# Stearns.net
KiCad netlist of a schematic drawn in EAGLE
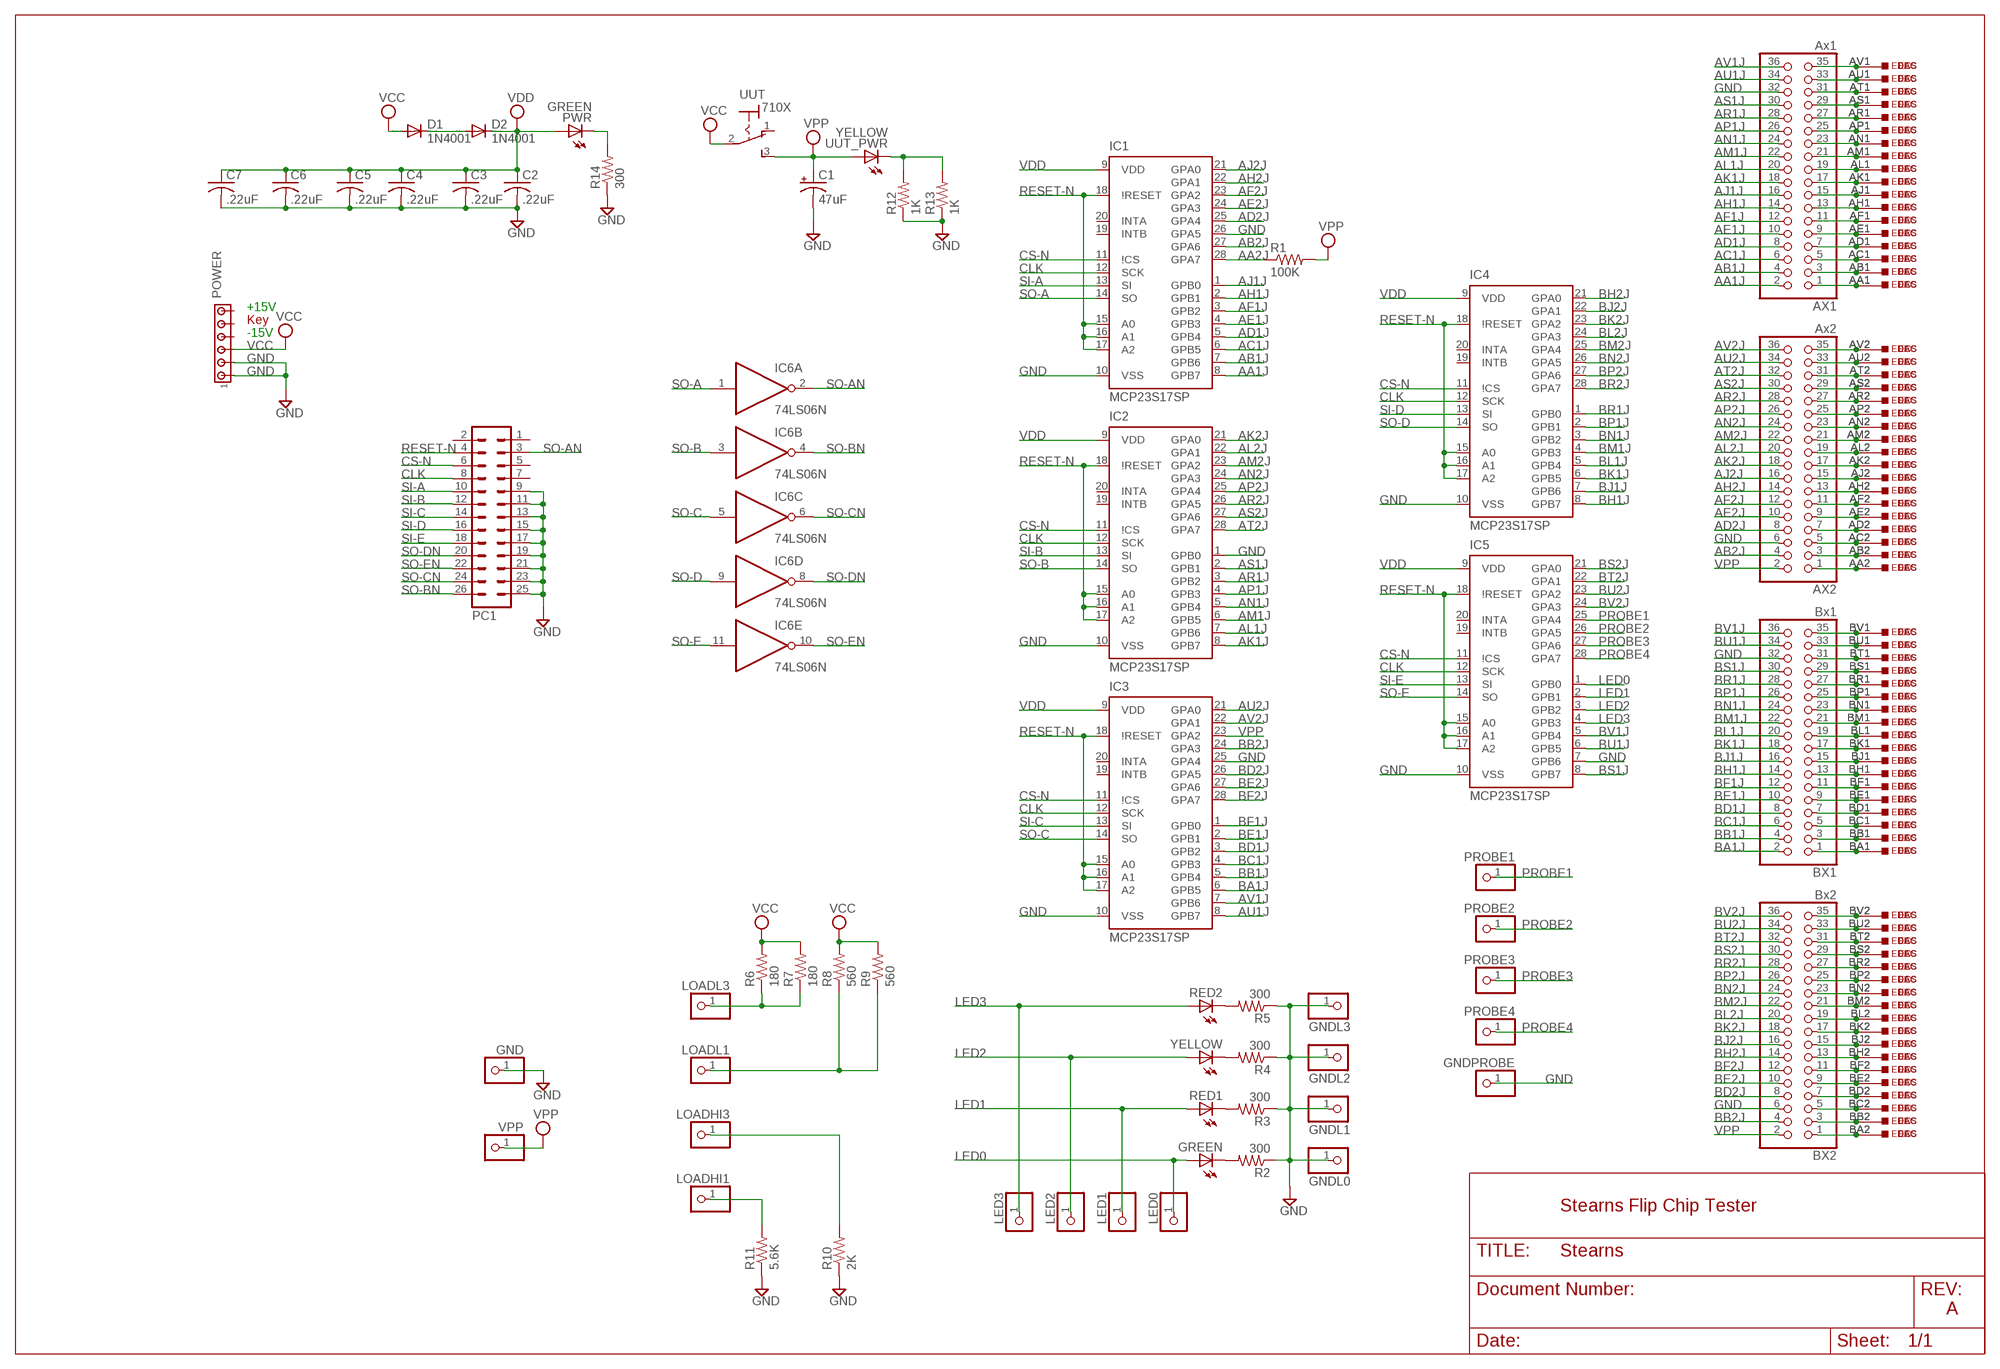
[diagram p0: schematic, sheet 1]

(export (version "E")
  (design (tool "Eeschema 10.0.6"))
  (components
    (comp (ref "AX1")
      (value "Ax1")
      (footprint "eagle-import:2X18")
      (libsource (lib "eagle-import") (part "PINHD-2X18"))
    )
    (comp (ref "AX2")
      (value "Ax2")
      (footprint "eagle-import:2X18")
      (libsource (lib "eagle-import") (part "PINHD-2X18"))
    )
    (comp (ref "BX1")
      (value "Bx1")
      (footprint "eagle-import:2X18")
      (libsource (lib "eagle-import") (part "PINHD-2X18"))
    )
    (comp (ref "BX2")
      (value "Bx2")
      (footprint "eagle-import:2X18")
      (libsource (lib "eagle-import") (part "PINHD-2X18"))
    )
    (comp (ref "C1")
      (value "47uF")
      (footprint "eagle-import:E5-8,5")
      (libsource (lib "eagle-import") (part "CPOL-USE5-8.5"))
    )
    (comp (ref "C2")
      (value ".22uF")
      (footprint "eagle-import:C050-025X075")
      (libsource (lib "eagle-import") (part "C-US050-025X075"))
    )
    (comp (ref "C3")
      (value ".22uF")
      (footprint "eagle-import:C050-025X075")
      (libsource (lib "eagle-import") (part "C-US050-025X075"))
    )
    (comp (ref "C4")
      (value ".22uF")
      (footprint "eagle-import:C050-025X075")
      (libsource (lib "eagle-import") (part "C-US050-025X075"))
    )
    (comp (ref "C5")
      (value ".22uF")
      (footprint "eagle-import:C050-025X075")
      (libsource (lib "eagle-import") (part "C-US050-025X075"))
    )
    (comp (ref "C6")
      (value ".22uF")
      (footprint "eagle-import:C050-025X075")
      (libsource (lib "eagle-import") (part "C-US050-025X075"))
    )
    (comp (ref "C7")
      (value ".22uF")
      (footprint "eagle-import:C050-025X075")
      (libsource (lib "eagle-import") (part "C-US050-025X075"))
    )
    (comp (ref "D1")
      (value "1N4001")
      (footprint "eagle-import:DO41-10")
      (libsource (lib "eagle-import") (part "1N4004"))
    )
    (comp (ref "D2")
      (value "1N4001")
      (footprint "eagle-import:DO41-10")
      (libsource (lib "eagle-import") (part "1N4004"))
    )
    (comp (ref "DEC")
      (value "W971")
      (footprint "eagle-import:H807-2")
      (libsource (lib "eagle-import") (part "W971"))
    )
    (comp (ref "ECS")
      (value "W971ECS")
      (footprint "eagle-import:ECS2418-2")
      (libsource (lib "eagle-import") (part "W971ECS"))
    )
    (comp (ref "EDAC")
      (value "W971EDAC")
      (footprint "eagle-import:EDAC346-36-2")
      (libsource (lib "eagle-import") (part "W971EDAC"))
    )
    (comp (ref "GND")
      (value "PINHD-1X1")
      (footprint "eagle-import:1X01")
      (libsource (lib "eagle-import") (part "PINHD-1X1"))
    )
    (comp (ref "GNDL0")
      (value "PINHD-1X1")
      (footprint "eagle-import:1X01")
      (libsource (lib "eagle-import") (part "PINHD-1X1"))
    )
    (comp (ref "GNDL1")
      (value "PINHD-1X1")
      (footprint "eagle-import:1X01")
      (libsource (lib "eagle-import") (part "PINHD-1X1"))
    )
    (comp (ref "GNDL2")
      (value "PINHD-1X1")
      (footprint "eagle-import:1X01")
      (libsource (lib "eagle-import") (part "PINHD-1X1"))
    )
    (comp (ref "GNDL3")
      (value "PINHD-1X1")
      (footprint "eagle-import:1X01")
      (libsource (lib "eagle-import") (part "PINHD-1X1"))
    )
    (comp (ref "GNDPROBE")
      (value "PINHD-1X1")
      (footprint "eagle-import:1X01")
      (libsource (lib "eagle-import") (part "PINHD-1X1"))
    )
    (comp (ref "GREEN")
      (value "LED5MM")
      (footprint "eagle-import:LED5MM")
      (libsource (lib "eagle-import") (part "LED5MM"))
    )
    (comp (ref "IC1")
      (value "MCP23S17SP")
      (footprint "eagle-import:DIL28-3")
      (libsource (lib "eagle-import") (part "MCP23S17SP"))
    )
    (comp (ref "IC2")
      (value "MCP23S17SP")
      (footprint "eagle-import:DIL28-3")
      (libsource (lib "eagle-import") (part "MCP23S17SP"))
    )
    (comp (ref "IC3")
      (value "MCP23S17SP")
      (footprint "eagle-import:DIL28-3")
      (libsource (lib "eagle-import") (part "MCP23S17SP"))
    )
    (comp (ref "IC4")
      (value "MCP23S17SP")
      (footprint "eagle-import:DIL28-3")
      (libsource (lib "eagle-import") (part "MCP23S17SP"))
    )
    (comp (ref "IC5")
      (value "MCP23S17SP")
      (footprint "eagle-import:DIL28-3")
      (libsource (lib "eagle-import") (part "MCP23S17SP"))
    )
    (comp (ref "IC6")
      (value "74LS06N")
      (footprint "eagle-import:DIL14")
      (libsource (lib "eagle-import") (part "7406NLS"))
    )
    (comp (ref "LED0")
      (value "PINHD-1X1")
      (footprint "eagle-import:1X01")
      (libsource (lib "eagle-import") (part "PINHD-1X1"))
    )
    (comp (ref "LED1")
      (value "PINHD-1X1")
      (footprint "eagle-import:1X01")
      (libsource (lib "eagle-import") (part "PINHD-1X1"))
    )
    (comp (ref "LED2")
      (value "PINHD-1X1")
      (footprint "eagle-import:1X01")
      (libsource (lib "eagle-import") (part "PINHD-1X1"))
    )
    (comp (ref "LED3")
      (value "PINHD-1X1")
      (footprint "eagle-import:1X01")
      (libsource (lib "eagle-import") (part "PINHD-1X1"))
    )
    (comp (ref "LOADHI1")
      (value "PINHD-1X1")
      (footprint "eagle-import:1X01")
      (libsource (lib "eagle-import") (part "PINHD-1X1"))
    )
    (comp (ref "LOADHI3")
      (value "PINHD-1X1")
      (footprint "eagle-import:1X01")
      (libsource (lib "eagle-import") (part "PINHD-1X1"))
    )
    (comp (ref "LOADL1")
      (value "PINHD-1X1")
      (footprint "eagle-import:1X01")
      (libsource (lib "eagle-import") (part "PINHD-1X1"))
    )
    (comp (ref "LOADL3")
      (value "PINHD-1X1")
      (footprint "eagle-import:1X01")
      (libsource (lib "eagle-import") (part "PINHD-1X1"))
    )
    (comp (ref "PC1")
      (value "MA13-2")
      (footprint "eagle-import:MA13-2")
      (libsource (lib "eagle-import") (part "MA13-2"))
    )
    (comp (ref "POWER")
      (value "MTA06-156")
      (footprint "eagle-import:1X6MTA")
      (libsource (lib "eagle-import") (part "MTA06-156"))
    )
    (comp (ref "PROBE1")
      (value "PINHD-1X1")
      (footprint "eagle-import:1X01")
      (libsource (lib "eagle-import") (part "PINHD-1X1"))
    )
    (comp (ref "PROBE2")
      (value "PINHD-1X1")
      (footprint "eagle-import:1X01")
      (libsource (lib "eagle-import") (part "PINHD-1X1"))
    )
    (comp (ref "PROBE3")
      (value "PINHD-1X1")
      (footprint "eagle-import:1X01")
      (libsource (lib "eagle-import") (part "PINHD-1X1"))
    )
    (comp (ref "PROBE4")
      (value "PINHD-1X1")
      (footprint "eagle-import:1X01")
      (libsource (lib "eagle-import") (part "PINHD-1X1"))
    )
    (comp (ref "PWR")
      (value "GREEN")
      (footprint "eagle-import:LED5MM")
      (libsource (lib "eagle-import") (part "LED5MM"))
    )
    (comp (ref "R1")
      (value "100K")
      (footprint "eagle-import:0207_10")
      (libsource (lib "eagle-import") (part "R-US_0207/10"))
    )
    (comp (ref "R2")
      (value "300")
      (footprint "eagle-import:0207_10")
      (libsource (lib "eagle-import") (part "R-US_0207/10"))
    )
    (comp (ref "R3")
      (value "300")
      (footprint "eagle-import:0207_10")
      (libsource (lib "eagle-import") (part "R-US_0207/10"))
    )
    (comp (ref "R4")
      (value "300")
      (footprint "eagle-import:0207_10")
      (libsource (lib "eagle-import") (part "R-US_0207/10"))
    )
    (comp (ref "R5")
      (value "300")
      (footprint "eagle-import:0207_10")
      (libsource (lib "eagle-import") (part "R-US_0207/10"))
    )
    (comp (ref "R6")
      (value "180")
      (footprint "eagle-import:0207_10")
      (libsource (lib "eagle-import") (part "R-US_0207/10"))
    )
    (comp (ref "R7")
      (value "180")
      (footprint "eagle-import:0207_10")
      (libsource (lib "eagle-import") (part "R-US_0207/10"))
    )
    (comp (ref "R8")
      (value "560")
      (footprint "eagle-import:0207_10")
      (libsource (lib "eagle-import") (part "R-US_0207/10"))
    )
    (comp (ref "R9")
      (value "560")
      (footprint "eagle-import:0207_10")
      (libsource (lib "eagle-import") (part "R-US_0207/10"))
    )
    (comp (ref "R10")
      (value "2K")
      (footprint "eagle-import:0207_10")
      (libsource (lib "eagle-import") (part "R-US_0207/10"))
    )
    (comp (ref "R11")
      (value "5.6K")
      (footprint "eagle-import:0207_10")
      (libsource (lib "eagle-import") (part "R-US_0207/10"))
    )
    (comp (ref "R12")
      (value "1K")
      (footprint "eagle-import:0207_10")
      (libsource (lib "eagle-import") (part "R-US_0207/10"))
    )
    (comp (ref "R13")
      (value "1K")
      (footprint "eagle-import:0207_10")
      (libsource (lib "eagle-import") (part "R-US_0207/10"))
    )
    (comp (ref "R14")
      (value "300")
      (footprint "eagle-import:0207_10")
      (libsource (lib "eagle-import") (part "R-US_0207/10"))
    )
    (comp (ref "RED1")
      (value "LED5MM")
      (footprint "eagle-import:LED5MM")
      (libsource (lib "eagle-import") (part "LED5MM"))
    )
    (comp (ref "RED2")
      (value "LED5MM")
      (footprint "eagle-import:LED5MM")
      (libsource (lib "eagle-import") (part "LED5MM"))
    )
    (comp (ref "UUT")
      (value "710X")
      (footprint "eagle-import:7109MD9V3")
      (libsource (lib "eagle-import") (part "710X"))
    )
    (comp (ref "UUT_PWR")
      (value "YELLOW")
      (footprint "eagle-import:LED5MM")
      (libsource (lib "eagle-import") (part "LED5MM"))
    )
    (comp (ref "VPP")
      (value "PINHD-1X1")
      (footprint "eagle-import:1X01")
      (libsource (lib "eagle-import") (part "PINHD-1X1"))
    )
    (comp (ref "YELLOW")
      (value "LED5MM")
      (footprint "eagle-import:LED5MM")
      (libsource (lib "eagle-import") (part "LED5MM"))
    )
  )
  (nets
    (net (code "1") (name "/AA1J") (class "Default")
      (node (ref "AX1") (pin "2") (pinfunction "2_2") (pintype "passive"))
      (node (ref "IC1") (pin "8") (pinfunction "GPB7_8") (pintype "bidirectional"))
    )
    (net (code "2") (name "/AA2J") (class "Default")
      (node (ref "IC1") (pin "28") (pinfunction "GPA7_28") (pintype "bidirectional"))
      (node (ref "R1") (pin "1") (pinfunction "1_1") (pintype "passive"))
    )
    (net (code "3") (name "/AB1J") (class "Default")
      (node (ref "AX1") (pin "4") (pinfunction "4_4") (pintype "passive"))
      (node (ref "IC1") (pin "7") (pinfunction "GPB6_7") (pintype "bidirectional"))
    )
    (net (code "4") (name "/AB2J") (class "Default")
      (node (ref "AX2") (pin "4") (pinfunction "4_4") (pintype "passive"))
      (node (ref "IC1") (pin "27") (pinfunction "GPA6_27") (pintype "bidirectional"))
    )
    (net (code "5") (name "/AC1J") (class "Default")
      (node (ref "AX1") (pin "6") (pinfunction "6_6") (pintype "passive"))
      (node (ref "IC1") (pin "6") (pinfunction "GPB5_6") (pintype "bidirectional"))
    )
    (net (code "6") (name "/AD1J") (class "Default")
      (node (ref "AX1") (pin "8") (pinfunction "8_8") (pintype "passive"))
      (node (ref "IC1") (pin "5") (pinfunction "GPB4_5") (pintype "bidirectional"))
    )
    (net (code "7") (name "/AD2J") (class "Default")
      (node (ref "AX2") (pin "8") (pinfunction "8_8") (pintype "passive"))
      (node (ref "IC1") (pin "25") (pinfunction "GPA4_25") (pintype "bidirectional"))
    )
    (net (code "8") (name "/AE1J") (class "Default")
      (node (ref "AX1") (pin "10") (pinfunction "10_10") (pintype "passive"))
      (node (ref "IC1") (pin "4") (pinfunction "GPB3_4") (pintype "bidirectional"))
    )
    (net (code "9") (name "/AE2J") (class "Default")
      (node (ref "AX2") (pin "10") (pinfunction "10_10") (pintype "passive"))
      (node (ref "IC1") (pin "24") (pinfunction "GPA3_24") (pintype "bidirectional"))
    )
    (net (code "10") (name "/AF1J") (class "Default")
      (node (ref "AX1") (pin "12") (pinfunction "12_12") (pintype "passive"))
      (node (ref "IC1") (pin "3") (pinfunction "GPB2_3") (pintype "bidirectional"))
    )
    (net (code "11") (name "/AF2J") (class "Default")
      (node (ref "AX2") (pin "12") (pinfunction "12_12") (pintype "passive"))
      (node (ref "IC1") (pin "23") (pinfunction "GPA2_23") (pintype "bidirectional"))
    )
    (net (code "12") (name "/AH1J") (class "Default")
      (node (ref "AX1") (pin "14") (pinfunction "14_14") (pintype "passive"))
      (node (ref "IC1") (pin "2") (pinfunction "GPB1_2") (pintype "bidirectional"))
    )
    (net (code "13") (name "/AH2J") (class "Default")
      (node (ref "AX2") (pin "14") (pinfunction "14_14") (pintype "passive"))
      (node (ref "IC1") (pin "22") (pinfunction "GPA1_22") (pintype "bidirectional"))
    )
    (net (code "14") (name "/AJ1J") (class "Default")
      (node (ref "AX1") (pin "16") (pinfunction "16_16") (pintype "passive"))
      (node (ref "IC1") (pin "1") (pinfunction "GPB0_1") (pintype "bidirectional"))
    )
    (net (code "15") (name "/AJ2J") (class "Default")
      (node (ref "AX2") (pin "16") (pinfunction "16_16") (pintype "passive"))
      (node (ref "IC1") (pin "21") (pinfunction "GPA0_21") (pintype "bidirectional"))
    )
    (net (code "16") (name "/AK1J") (class "Default")
      (node (ref "AX1") (pin "18") (pinfunction "18_18") (pintype "passive"))
      (node (ref "IC2") (pin "8") (pinfunction "GPB7_8") (pintype "bidirectional"))
    )
    (net (code "17") (name "/AK2J") (class "Default")
      (node (ref "AX2") (pin "18") (pinfunction "18_18") (pintype "passive"))
      (node (ref "IC2") (pin "21") (pinfunction "GPA0_21") (pintype "bidirectional"))
    )
    (net (code "18") (name "/AL1J") (class "Default")
      (node (ref "AX1") (pin "20") (pinfunction "20_20") (pintype "passive"))
      (node (ref "IC2") (pin "7") (pinfunction "GPB6_7") (pintype "bidirectional"))
    )
    (net (code "19") (name "/AL2J") (class "Default")
      (node (ref "AX2") (pin "20") (pinfunction "20_20") (pintype "passive"))
      (node (ref "IC2") (pin "22") (pinfunction "GPA1_22") (pintype "bidirectional"))
    )
    (net (code "20") (name "/AM1J") (class "Default")
      (node (ref "AX1") (pin "22") (pinfunction "22_22") (pintype "passive"))
      (node (ref "IC2") (pin "6") (pinfunction "GPB5_6") (pintype "bidirectional"))
    )
    (net (code "21") (name "/AM2J") (class "Default")
      (node (ref "AX2") (pin "22") (pinfunction "22_22") (pintype "passive"))
      (node (ref "IC2") (pin "23") (pinfunction "GPA2_23") (pintype "bidirectional"))
    )
    (net (code "22") (name "/AN1J") (class "Default")
      (node (ref "AX1") (pin "24") (pinfunction "24_24") (pintype "passive"))
      (node (ref "IC2") (pin "5") (pinfunction "GPB4_5") (pintype "bidirectional"))
    )
    (net (code "23") (name "/AN2J") (class "Default")
      (node (ref "AX2") (pin "24") (pinfunction "24_24") (pintype "passive"))
      (node (ref "IC2") (pin "24") (pinfunction "GPA3_24") (pintype "bidirectional"))
    )
    (net (code "24") (name "/AP1J") (class "Default")
      (node (ref "AX1") (pin "26") (pinfunction "26_26") (pintype "passive"))
      (node (ref "IC2") (pin "4") (pinfunction "GPB3_4") (pintype "bidirectional"))
    )
    (net (code "25") (name "/AP2J") (class "Default")
      (node (ref "AX2") (pin "26") (pinfunction "26_26") (pintype "passive"))
      (node (ref "IC2") (pin "25") (pinfunction "GPA4_25") (pintype "bidirectional"))
    )
    (net (code "26") (name "/AR1J") (class "Default")
      (node (ref "AX1") (pin "28") (pinfunction "28_28") (pintype "passive"))
      (node (ref "IC2") (pin "3") (pinfunction "GPB2_3") (pintype "bidirectional"))
    )
    (net (code "27") (name "/AR2J") (class "Default")
      (node (ref "AX2") (pin "28") (pinfunction "28_28") (pintype "passive"))
      (node (ref "IC2") (pin "26") (pinfunction "GPA5_26") (pintype "bidirectional"))
    )
    (net (code "28") (name "/AS1J") (class "Default")
      (node (ref "AX1") (pin "30") (pinfunction "30_30") (pintype "passive"))
      (node (ref "IC2") (pin "2") (pinfunction "GPB1_2") (pintype "bidirectional"))
    )
    (net (code "29") (name "/AS2J") (class "Default")
      (node (ref "AX2") (pin "30") (pinfunction "30_30") (pintype "passive"))
      (node (ref "IC2") (pin "27") (pinfunction "GPA6_27") (pintype "bidirectional"))
    )
    (net (code "30") (name "/AT2J") (class "Default")
      (node (ref "AX2") (pin "32") (pinfunction "32_32") (pintype "passive"))
      (node (ref "IC2") (pin "28") (pinfunction "GPA7_28") (pintype "bidirectional"))
    )
    (net (code "31") (name "/AU1J") (class "Default")
      (node (ref "AX1") (pin "34") (pinfunction "34_34") (pintype "passive"))
      (node (ref "IC3") (pin "8") (pinfunction "GPB7_8") (pintype "bidirectional"))
    )
    (net (code "32") (name "/AU2J") (class "Default")
      (node (ref "AX2") (pin "34") (pinfunction "34_34") (pintype "passive"))
      (node (ref "IC3") (pin "21") (pinfunction "GPA0_21") (pintype "bidirectional"))
    )
    (net (code "33") (name "/AV1J") (class "Default")
      (node (ref "AX1") (pin "36") (pinfunction "36_36") (pintype "passive"))
      (node (ref "IC3") (pin "7") (pinfunction "GPB6_7") (pintype "bidirectional"))
    )
    (net (code "34") (name "/AV2J") (class "Default")
      (node (ref "AX2") (pin "36") (pinfunction "36_36") (pintype "passive"))
      (node (ref "IC3") (pin "22") (pinfunction "GPA1_22") (pintype "bidirectional"))
    )
    (net (code "35") (name "/BA1J") (class "Default")
      (node (ref "BX1") (pin "2") (pinfunction "2_2") (pintype "passive"))
      (node (ref "IC3") (pin "6") (pinfunction "GPB5_6") (pintype "bidirectional"))
    )
    (net (code "36") (name "/BB1J") (class "Default")
      (node (ref "BX1") (pin "4") (pinfunction "4_4") (pintype "passive"))
      (node (ref "IC3") (pin "5") (pinfunction "GPB4_5") (pintype "bidirectional"))
    )
    (net (code "37") (name "/BB2J") (class "Default")
      (node (ref "BX2") (pin "4") (pinfunction "4_4") (pintype "passive"))
      (node (ref "IC3") (pin "24") (pinfunction "GPA3_24") (pintype "bidirectional"))
    )
    (net (code "38") (name "/BC1J") (class "Default")
      (node (ref "BX1") (pin "6") (pinfunction "6_6") (pintype "passive"))
      (node (ref "IC3") (pin "4") (pinfunction "GPB3_4") (pintype "bidirectional"))
    )
    (net (code "39") (name "/BD1J") (class "Default")
      (node (ref "BX1") (pin "8") (pinfunction "8_8") (pintype "passive"))
      (node (ref "IC3") (pin "3") (pinfunction "GPB2_3") (pintype "bidirectional"))
    )
    (net (code "40") (name "/BD2J") (class "Default")
      (node (ref "BX2") (pin "8") (pinfunction "8_8") (pintype "passive"))
      (node (ref "IC3") (pin "26") (pinfunction "GPA5_26") (pintype "bidirectional"))
    )
    (net (code "41") (name "/BE1J") (class "Default")
      (node (ref "BX1") (pin "10") (pinfunction "10_10") (pintype "passive"))
      (node (ref "IC3") (pin "2") (pinfunction "GPB1_2") (pintype "bidirectional"))
    )
    (net (code "42") (name "/BE2J") (class "Default")
      (node (ref "BX2") (pin "10") (pinfunction "10_10") (pintype "passive"))
      (node (ref "IC3") (pin "27") (pinfunction "GPA6_27") (pintype "bidirectional"))
    )
    (net (code "43") (name "/BF1J") (class "Default")
      (node (ref "BX1") (pin "12") (pinfunction "12_12") (pintype "passive"))
      (node (ref "IC3") (pin "1") (pinfunction "GPB0_1") (pintype "bidirectional"))
    )
    (net (code "44") (name "/BF2J") (class "Default")
      (node (ref "BX2") (pin "12") (pinfunction "12_12") (pintype "passive"))
      (node (ref "IC3") (pin "28") (pinfunction "GPA7_28") (pintype "bidirectional"))
    )
    (net (code "45") (name "/BH1J") (class "Default")
      (node (ref "BX1") (pin "14") (pinfunction "14_14") (pintype "passive"))
      (node (ref "IC4") (pin "8") (pinfunction "GPB7_8") (pintype "bidirectional"))
    )
    (net (code "46") (name "/BH2J") (class "Default")
      (node (ref "BX2") (pin "14") (pinfunction "14_14") (pintype "passive"))
      (node (ref "IC4") (pin "21") (pinfunction "GPA0_21") (pintype "bidirectional"))
    )
    (net (code "47") (name "/BJ1J") (class "Default")
      (node (ref "BX1") (pin "16") (pinfunction "16_16") (pintype "passive"))
      (node (ref "IC4") (pin "7") (pinfunction "GPB6_7") (pintype "bidirectional"))
    )
    (net (code "48") (name "/BJ2J") (class "Default")
      (node (ref "BX2") (pin "16") (pinfunction "16_16") (pintype "passive"))
      (node (ref "IC4") (pin "22") (pinfunction "GPA1_22") (pintype "bidirectional"))
    )
    (net (code "49") (name "/BK1J") (class "Default")
      (node (ref "BX1") (pin "18") (pinfunction "18_18") (pintype "passive"))
      (node (ref "IC4") (pin "6") (pinfunction "GPB5_6") (pintype "bidirectional"))
    )
    (net (code "50") (name "/BK2J") (class "Default")
      (node (ref "BX2") (pin "18") (pinfunction "18_18") (pintype "passive"))
      (node (ref "IC4") (pin "23") (pinfunction "GPA2_23") (pintype "bidirectional"))
    )
    (net (code "51") (name "/BL1J") (class "Default")
      (node (ref "BX1") (pin "20") (pinfunction "20_20") (pintype "passive"))
      (node (ref "IC4") (pin "5") (pinfunction "GPB4_5") (pintype "bidirectional"))
    )
    (net (code "52") (name "/BL2J") (class "Default")
      (node (ref "BX2") (pin "20") (pinfunction "20_20") (pintype "passive"))
      (node (ref "IC4") (pin "24") (pinfunction "GPA3_24") (pintype "bidirectional"))
    )
    (net (code "53") (name "/BM1J") (class "Default")
      (node (ref "BX1") (pin "22") (pinfunction "22_22") (pintype "passive"))
      (node (ref "IC4") (pin "4") (pinfunction "GPB3_4") (pintype "bidirectional"))
    )
    (net (code "54") (name "/BM2J") (class "Default")
      (node (ref "BX2") (pin "22") (pinfunction "22_22") (pintype "passive"))
      (node (ref "IC4") (pin "25") (pinfunction "GPA4_25") (pintype "bidirectional"))
    )
    (net (code "55") (name "/BN1J") (class "Default")
      (node (ref "BX1") (pin "24") (pinfunction "24_24") (pintype "passive"))
      (node (ref "IC4") (pin "3") (pinfunction "GPB2_3") (pintype "bidirectional"))
    )
    (net (code "56") (name "/BN2J") (class "Default")
      (node (ref "BX2") (pin "24") (pinfunction "24_24") (pintype "passive"))
      (node (ref "IC4") (pin "26") (pinfunction "GPA5_26") (pintype "bidirectional"))
    )
    (net (code "57") (name "/BP1J") (class "Default")
      (node (ref "BX1") (pin "26") (pinfunction "26_26") (pintype "passive"))
      (node (ref "IC4") (pin "2") (pinfunction "GPB1_2") (pintype "bidirectional"))
    )
    (net (code "58") (name "/BP2J") (class "Default")
      (node (ref "BX2") (pin "26") (pinfunction "26_26") (pintype "passive"))
      (node (ref "IC4") (pin "27") (pinfunction "GPA6_27") (pintype "bidirectional"))
    )
    (net (code "59") (name "/BR1J") (class "Default")
      (node (ref "BX1") (pin "28") (pinfunction "28_28") (pintype "passive"))
      (node (ref "IC4") (pin "1") (pinfunction "GPB0_1") (pintype "bidirectional"))
    )
    (net (code "60") (name "/BR2J") (class "Default")
      (node (ref "BX2") (pin "28") (pinfunction "28_28") (pintype "passive"))
      (node (ref "IC4") (pin "28") (pinfunction "GPA7_28") (pintype "bidirectional"))
    )
    (net (code "61") (name "/BS1J") (class "Default")
      (node (ref "BX1") (pin "30") (pinfunction "30_30") (pintype "passive"))
      (node (ref "IC5") (pin "8") (pinfunction "GPB7_8") (pintype "bidirectional"))
    )
    (net (code "62") (name "/BS2J") (class "Default")
      (node (ref "BX2") (pin "30") (pinfunction "30_30") (pintype "passive"))
      (node (ref "IC5") (pin "21") (pinfunction "GPA0_21") (pintype "bidirectional"))
    )
    (net (code "63") (name "/BT2J") (class "Default")
      (node (ref "BX2") (pin "32") (pinfunction "32_32") (pintype "passive"))
      (node (ref "IC5") (pin "22") (pinfunction "GPA1_22") (pintype "bidirectional"))
    )
    (net (code "64") (name "/BU1J") (class "Default")
      (node (ref "BX1") (pin "34") (pinfunction "34_34") (pintype "passive"))
      (node (ref "IC5") (pin "6") (pinfunction "GPB5_6") (pintype "bidirectional"))
    )
    (net (code "65") (name "/BU2J") (class "Default")
      (node (ref "BX2") (pin "34") (pinfunction "34_34") (pintype "passive"))
      (node (ref "IC5") (pin "23") (pinfunction "GPA2_23") (pintype "bidirectional"))
    )
    (net (code "66") (name "/BV1J") (class "Default")
      (node (ref "BX1") (pin "36") (pinfunction "36_36") (pintype "passive"))
      (node (ref "IC5") (pin "5") (pinfunction "GPB4_5") (pintype "bidirectional"))
    )
    (net (code "67") (name "/BV2J") (class "Default")
      (node (ref "BX2") (pin "36") (pinfunction "36_36") (pintype "passive"))
      (node (ref "IC5") (pin "24") (pinfunction "GPA3_24") (pintype "bidirectional"))
    )
    (net (code "68") (name "/CLK") (class "Default")
      (node (ref "IC1") (pin "12") (pinfunction "SCK_12") (pintype "input"))
      (node (ref "IC2") (pin "12") (pinfunction "SCK_12") (pintype "input"))
      (node (ref "IC3") (pin "12") (pinfunction "SCK_12") (pintype "input"))
      (node (ref "IC4") (pin "12") (pinfunction "SCK_12") (pintype "input"))
      (node (ref "IC5") (pin "12") (pinfunction "SCK_12") (pintype "input"))
      (node (ref "PC1") (pin "8") (pinfunction "8_8") (pintype "passive"))
    )
    (net (code "69") (name "/CS-N") (class "Default")
      (node (ref "IC1") (pin "11") (pinfunction "\\~{CS}_11") (pintype "input"))
      (node (ref "IC2") (pin "11") (pinfunction "\\~{CS}_11") (pintype "input"))
      (node (ref "IC3") (pin "11") (pinfunction "\\~{CS}_11") (pintype "input"))
      (node (ref "IC4") (pin "11") (pinfunction "\\~{CS}_11") (pintype "input"))
      (node (ref "IC5") (pin "11") (pinfunction "\\~{CS}_11") (pintype "input"))
      (node (ref "PC1") (pin "6") (pinfunction "6_6") (pintype "passive"))
    )
    (net (code "70") (name "/LED0") (class "Default")
      (node (ref "GREEN") (pin "A") (pinfunction "A_A") (pintype "passive"))
      (node (ref "IC5") (pin "1") (pinfunction "GPB0_1") (pintype "bidirectional"))
      (node (ref "LED0") (pin "1") (pinfunction "1_1") (pintype "passive"))
    )
    (net (code "71") (name "/LED1") (class "Default")
      (node (ref "IC5") (pin "2") (pinfunction "GPB1_2") (pintype "bidirectional"))
      (node (ref "LED1") (pin "1") (pinfunction "1_1") (pintype "passive"))
      (node (ref "RED1") (pin "A") (pinfunction "A_A") (pintype "passive"))
    )
    (net (code "72") (name "/LED2") (class "Default")
      (node (ref "IC5") (pin "3") (pinfunction "GPB2_3") (pintype "bidirectional"))
      (node (ref "LED2") (pin "1") (pinfunction "1_1") (pintype "passive"))
      (node (ref "YELLOW") (pin "A") (pinfunction "A_A") (pintype "passive"))
    )
    (net (code "73") (name "/LED3") (class "Default")
      (node (ref "IC5") (pin "4") (pinfunction "GPB3_4") (pintype "bidirectional"))
      (node (ref "LED3") (pin "1") (pinfunction "1_1") (pintype "passive"))
      (node (ref "RED2") (pin "A") (pinfunction "A_A") (pintype "passive"))
    )
    (net (code "74") (name "/PROBE1") (class "Default")
      (node (ref "IC5") (pin "25") (pinfunction "GPA4_25") (pintype "bidirectional"))
      (node (ref "PROBE1") (pin "1") (pinfunction "1_1") (pintype "passive"))
    )
    (net (code "75") (name "/PROBE2") (class "Default")
      (node (ref "IC5") (pin "26") (pinfunction "GPA5_26") (pintype "bidirectional"))
      (node (ref "PROBE2") (pin "1") (pinfunction "1_1") (pintype "passive"))
    )
    (net (code "76") (name "/PROBE3") (class "Default")
      (node (ref "IC5") (pin "27") (pinfunction "GPA6_27") (pintype "bidirectional"))
      (node (ref "PROBE3") (pin "1") (pinfunction "1_1") (pintype "passive"))
    )
    (net (code "77") (name "/PROBE4") (class "Default")
      (node (ref "IC5") (pin "28") (pinfunction "GPA7_28") (pintype "bidirectional"))
      (node (ref "PROBE4") (pin "1") (pinfunction "1_1") (pintype "passive"))
    )
    (net (code "78") (name "/RESET-N") (class "Default")
      (node (ref "IC1") (pin "15") (pinfunction "A0_15") (pintype "input"))
      (node (ref "IC1") (pin "16") (pinfunction "A1_16") (pintype "input"))
      (node (ref "IC1") (pin "17") (pinfunction "A2_17") (pintype "input"))
      (node (ref "IC1") (pin "18") (pinfunction "\\~{RESET}_18") (pintype "input"))
      (node (ref "IC2") (pin "15") (pinfunction "A0_15") (pintype "input"))
      (node (ref "IC2") (pin "16") (pinfunction "A1_16") (pintype "input"))
      (node (ref "IC2") (pin "17") (pinfunction "A2_17") (pintype "input"))
      (node (ref "IC2") (pin "18") (pinfunction "\\~{RESET}_18") (pintype "input"))
      (node (ref "IC3") (pin "15") (pinfunction "A0_15") (pintype "input"))
      (node (ref "IC3") (pin "16") (pinfunction "A1_16") (pintype "input"))
      (node (ref "IC3") (pin "17") (pinfunction "A2_17") (pintype "input"))
      (node (ref "IC3") (pin "18") (pinfunction "\\~{RESET}_18") (pintype "input"))
      (node (ref "IC4") (pin "15") (pinfunction "A0_15") (pintype "input"))
      (node (ref "IC4") (pin "16") (pinfunction "A1_16") (pintype "input"))
      (node (ref "IC4") (pin "17") (pinfunction "A2_17") (pintype "input"))
      (node (ref "IC4") (pin "18") (pinfunction "\\~{RESET}_18") (pintype "input"))
      (node (ref "IC5") (pin "15") (pinfunction "A0_15") (pintype "input"))
      (node (ref "IC5") (pin "16") (pinfunction "A1_16") (pintype "input"))
      (node (ref "IC5") (pin "17") (pinfunction "A2_17") (pintype "input"))
      (node (ref "IC5") (pin "18") (pinfunction "\\~{RESET}_18") (pintype "input"))
      (node (ref "PC1") (pin "4") (pinfunction "4_4") (pintype "passive"))
    )
    (net (code "79") (name "/SI-A") (class "Default")
      (node (ref "IC1") (pin "13") (pinfunction "SI_13") (pintype "input"))
      (node (ref "PC1") (pin "10") (pinfunction "10_10") (pintype "passive"))
    )
    (net (code "80") (name "/SI-B") (class "Default")
      (node (ref "IC2") (pin "13") (pinfunction "SI_13") (pintype "input"))
      (node (ref "PC1") (pin "12") (pinfunction "12_12") (pintype "passive"))
    )
    (net (code "81") (name "/SI-C") (class "Default")
      (node (ref "IC3") (pin "13") (pinfunction "SI_13") (pintype "input"))
      (node (ref "PC1") (pin "14") (pinfunction "14_14") (pintype "passive"))
    )
    (net (code "82") (name "/SI-D") (class "Default")
      (node (ref "IC4") (pin "13") (pinfunction "SI_13") (pintype "input"))
      (node (ref "PC1") (pin "16") (pinfunction "16_16") (pintype "passive"))
    )
    (net (code "83") (name "/SI-E") (class "Default")
      (node (ref "IC5") (pin "13") (pinfunction "SI_13") (pintype "input"))
      (node (ref "PC1") (pin "18") (pinfunction "18_18") (pintype "passive"))
    )
    (net (code "84") (name "/SO-A") (class "Default")
      (node (ref "IC1") (pin "14") (pinfunction "SO_14") (pintype "output"))
      (node (ref "IC6") (pin "1") (pinfunction "I_1") (pintype "input"))
    )
    (net (code "85") (name "/SO-AN") (class "Default")
      (node (ref "IC6") (pin "2") (pinfunction "O_2") (pintype "open_collector"))
      (node (ref "PC1") (pin "3") (pinfunction "3_3") (pintype "passive"))
    )
    (net (code "86") (name "/SO-B") (class "Default")
      (node (ref "IC2") (pin "14") (pinfunction "SO_14") (pintype "output"))
      (node (ref "IC6") (pin "3") (pinfunction "I_3") (pintype "input"))
    )
    (net (code "87") (name "/SO-BN") (class "Default")
      (node (ref "IC6") (pin "4") (pinfunction "O_4") (pintype "open_collector"))
      (node (ref "PC1") (pin "26") (pinfunction "26_26") (pintype "passive"))
    )
    (net (code "88") (name "/SO-C") (class "Default")
      (node (ref "IC3") (pin "14") (pinfunction "SO_14") (pintype "output"))
      (node (ref "IC6") (pin "5") (pinfunction "I_5") (pintype "input"))
    )
    (net (code "89") (name "/SO-CN") (class "Default")
      (node (ref "IC6") (pin "6") (pinfunction "O_6") (pintype "open_collector"))
      (node (ref "PC1") (pin "24") (pinfunction "24_24") (pintype "passive"))
    )
    (net (code "90") (name "/SO-D") (class "Default")
      (node (ref "IC4") (pin "14") (pinfunction "SO_14") (pintype "output"))
      (node (ref "IC6") (pin "9") (pinfunction "I_9") (pintype "input"))
    )
    (net (code "91") (name "/SO-DN") (class "Default")
      (node (ref "IC6") (pin "8") (pinfunction "O_8") (pintype "open_collector"))
      (node (ref "PC1") (pin "20") (pinfunction "20_20") (pintype "passive"))
    )
    (net (code "92") (name "/SO-E") (class "Default")
      (node (ref "IC5") (pin "14") (pinfunction "SO_14") (pintype "output"))
      (node (ref "IC6") (pin "11") (pinfunction "I_11") (pintype "input"))
    )
    (net (code "93") (name "/SO-EN") (class "Default")
      (node (ref "IC6") (pin "10") (pinfunction "O_10") (pintype "open_collector"))
      (node (ref "PC1") (pin "22") (pinfunction "22_22") (pintype "passive"))
    )
    (net (code "94") (name "GND") (class "Default")
      (node (ref "AX1") (pin "32") (pinfunction "32_32") (pintype "passive"))
      (node (ref "AX2") (pin "6") (pinfunction "6_6") (pintype "passive"))
      (node (ref "BX1") (pin "32") (pinfunction "32_32") (pintype "passive"))
      (node (ref "BX2") (pin "6") (pinfunction "6_6") (pintype "passive"))
      (node (ref "C1") (pin "-") (pinfunction "-_-") (pintype "passive"))
      (node (ref "C2") (pin "2") (pinfunction "2_2") (pintype "passive"))
      (node (ref "C3") (pin "2") (pinfunction "2_2") (pintype "passive"))
      (node (ref "C4") (pin "2") (pinfunction "2_2") (pintype "passive"))
      (node (ref "C5") (pin "2") (pinfunction "2_2") (pintype "passive"))
      (node (ref "C6") (pin "2") (pinfunction "2_2") (pintype "passive"))
      (node (ref "C7") (pin "2") (pinfunction "2_2") (pintype "passive"))
      (node (ref "GND") (pin "1") (pinfunction "1_1") (pintype "passive"))
      (node (ref "GNDL0") (pin "1") (pinfunction "1_1") (pintype "passive"))
      (node (ref "GNDL1") (pin "1") (pinfunction "1_1") (pintype "passive"))
      (node (ref "GNDL2") (pin "1") (pinfunction "1_1") (pintype "passive"))
      (node (ref "GNDL3") (pin "1") (pinfunction "1_1") (pintype "passive"))
      (node (ref "GNDPROBE") (pin "1") (pinfunction "1_1") (pintype "passive"))
      (node (ref "IC1") (pin "10") (pinfunction "VSS_10") (pintype "power_in"))
      (node (ref "IC1") (pin "26") (pinfunction "GPA5_26") (pintype "bidirectional"))
      (node (ref "IC2") (pin "1") (pinfunction "GPB0_1") (pintype "bidirectional"))
      (node (ref "IC2") (pin "10") (pinfunction "VSS_10") (pintype "power_in"))
      (node (ref "IC3") (pin "10") (pinfunction "VSS_10") (pintype "power_in"))
      (node (ref "IC3") (pin "25") (pinfunction "GPA4_25") (pintype "bidirectional"))
      (node (ref "IC4") (pin "10") (pinfunction "VSS_10") (pintype "power_in"))
      (node (ref "IC5") (pin "10") (pinfunction "VSS_10") (pintype "power_in"))
      (node (ref "IC5") (pin "7") (pinfunction "GPB6_7") (pintype "bidirectional"))
      (node (ref "PC1") (pin "11") (pinfunction "11_11") (pintype "passive"))
      (node (ref "PC1") (pin "13") (pinfunction "13_13") (pintype "passive"))
      (node (ref "PC1") (pin "15") (pinfunction "15_15") (pintype "passive"))
      (node (ref "PC1") (pin "17") (pinfunction "17_17") (pintype "passive"))
      (node (ref "PC1") (pin "19") (pinfunction "19_19") (pintype "passive"))
      (node (ref "PC1") (pin "21") (pinfunction "21_21") (pintype "passive"))
      (node (ref "PC1") (pin "23") (pinfunction "23_23") (pintype "passive"))
      (node (ref "PC1") (pin "25") (pinfunction "25_25") (pintype "passive"))
      (node (ref "PC1") (pin "9") (pinfunction "9_9") (pintype "passive"))
      (node (ref "POWER") (pin "1") (pinfunction "1_1") (pintype "passive"))
      (node (ref "POWER") (pin "2") (pinfunction "2_2") (pintype "passive"))
      (node (ref "R10") (pin "1") (pinfunction "1_1") (pintype "passive"))
      (node (ref "R11") (pin "1") (pinfunction "1_1") (pintype "passive"))
      (node (ref "R12") (pin "1") (pinfunction "1_1") (pintype "passive"))
      (node (ref "R13") (pin "1") (pinfunction "1_1") (pintype "passive"))
      (node (ref "R14") (pin "1") (pinfunction "1_1") (pintype "passive"))
      (node (ref "R2") (pin "1") (pinfunction "1_1") (pintype "passive"))
      (node (ref "R3") (pin "1") (pinfunction "1_1") (pintype "passive"))
      (node (ref "R4") (pin "1") (pinfunction "1_1") (pintype "passive"))
      (node (ref "R5") (pin "1") (pinfunction "1_1") (pintype "passive"))
    )
    (net (code "95") (name "Net-(D1-PadC)") (class "Default")
      (node (ref "D1") (pin "C") (pinfunction "C_C") (pintype "passive"))
      (node (ref "D2") (pin "A") (pinfunction "A_A") (pintype "passive"))
    )
    (net (code "96") (name "Net-(DECA-P$2)") (class "Default")
      (node (ref "AX1") (pin "1") (pinfunction "1_1") (pintype "passive"))
      (node (ref "DEC") (pin "AA1") (pinfunction "P$2_AA1") (pintype "bidirectional"))
      (node (ref "ECS") (pin "AA1") (pinfunction "P$2_AA1") (pintype "bidirectional"))
      (node (ref "EDAC") (pin "AA1") (pinfunction "P$2_AA1") (pintype "bidirectional"))
    )
    (net (code "97") (name "Net-(DECAA-P$2)") (class "Default")
      (node (ref "AX1") (pin "27") (pinfunction "27_27") (pintype "passive"))
      (node (ref "DEC") (pin "AR1") (pinfunction "P$2_AR1") (pintype "bidirectional"))
      (node (ref "ECS") (pin "AR1") (pinfunction "P$2_AR1") (pintype "bidirectional"))
      (node (ref "EDAC") (pin "AR1") (pinfunction "P$2_AR1") (pintype "bidirectional"))
    )
    (net (code "98") (name "Net-(DECAB-P$2)") (class "Default")
      (node (ref "AX2") (pin "27") (pinfunction "27_27") (pintype "passive"))
      (node (ref "DEC") (pin "AR2") (pinfunction "P$2_AR2") (pintype "bidirectional"))
      (node (ref "ECS") (pin "AR2") (pinfunction "P$2_AR2") (pintype "bidirectional"))
      (node (ref "EDAC") (pin "AR2") (pinfunction "P$2_AR2") (pintype "bidirectional"))
    )
    (net (code "99") (name "Net-(DECAC-P$2)") (class "Default")
      (node (ref "AX1") (pin "29") (pinfunction "29_29") (pintype "passive"))
      (node (ref "DEC") (pin "AS1") (pinfunction "P$2_AS1") (pintype "bidirectional"))
      (node (ref "ECS") (pin "AS1") (pinfunction "P$2_AS1") (pintype "bidirectional"))
      (node (ref "EDAC") (pin "AS1") (pinfunction "P$2_AS1") (pintype "bidirectional"))
    )
    (net (code "100") (name "Net-(DECAD-P$2)") (class "Default")
      (node (ref "AX2") (pin "29") (pinfunction "29_29") (pintype "passive"))
      (node (ref "DEC") (pin "AS2") (pinfunction "P$2_AS2") (pintype "bidirectional"))
      (node (ref "ECS") (pin "AS2") (pinfunction "P$2_AS2") (pintype "bidirectional"))
      (node (ref "EDAC") (pin "AS2") (pinfunction "P$2_AS2") (pintype "bidirectional"))
    )
    (net (code "101") (name "Net-(DECAE-P$2)") (class "Default")
      (node (ref "AX1") (pin "31") (pinfunction "31_31") (pintype "passive"))
      (node (ref "DEC") (pin "AT1") (pinfunction "P$2_AT1") (pintype "bidirectional"))
      (node (ref "ECS") (pin "AT1") (pinfunction "P$2_AT1") (pintype "bidirectional"))
      (node (ref "EDAC") (pin "AT1") (pinfunction "P$2_AT1") (pintype "bidirectional"))
    )
    (net (code "102") (name "Net-(DECAF-P$2)") (class "Default")
      (node (ref "AX2") (pin "31") (pinfunction "31_31") (pintype "passive"))
      (node (ref "DEC") (pin "AT2") (pinfunction "P$2_AT2") (pintype "bidirectional"))
      (node (ref "ECS") (pin "AT2") (pinfunction "P$2_AT2") (pintype "bidirectional"))
      (node (ref "EDAC") (pin "AT2") (pinfunction "P$2_AT2") (pintype "bidirectional"))
    )
    (net (code "103") (name "Net-(DECAG-P$2)") (class "Default")
      (node (ref "AX1") (pin "33") (pinfunction "33_33") (pintype "passive"))
      (node (ref "DEC") (pin "AU1") (pinfunction "P$2_AU1") (pintype "bidirectional"))
      (node (ref "ECS") (pin "AU1") (pinfunction "P$2_AU1") (pintype "bidirectional"))
      (node (ref "EDAC") (pin "AU1") (pinfunction "P$2_AU1") (pintype "bidirectional"))
    )
    (net (code "104") (name "Net-(DECAH-P$2)") (class "Default")
      (node (ref "AX2") (pin "33") (pinfunction "33_33") (pintype "passive"))
      (node (ref "DEC") (pin "AU2") (pinfunction "P$2_AU2") (pintype "bidirectional"))
      (node (ref "ECS") (pin "AU2") (pinfunction "P$2_AU2") (pintype "bidirectional"))
      (node (ref "EDAC") (pin "AU2") (pinfunction "P$2_AU2") (pintype "bidirectional"))
    )
    (net (code "105") (name "Net-(DECAI-P$2)") (class "Default")
      (node (ref "AX1") (pin "35") (pinfunction "35_35") (pintype "passive"))
      (node (ref "DEC") (pin "AV1") (pinfunction "P$2_AV1") (pintype "bidirectional"))
      (node (ref "ECS") (pin "AV1") (pinfunction "P$2_AV1") (pintype "bidirectional"))
      (node (ref "EDAC") (pin "AV1") (pinfunction "P$2_AV1") (pintype "bidirectional"))
    )
    (net (code "106") (name "Net-(DECAJ-P$2)") (class "Default")
      (node (ref "AX2") (pin "35") (pinfunction "35_35") (pintype "passive"))
      (node (ref "DEC") (pin "AV2") (pinfunction "P$2_AV2") (pintype "bidirectional"))
      (node (ref "ECS") (pin "AV2") (pinfunction "P$2_AV2") (pintype "bidirectional"))
      (node (ref "EDAC") (pin "AV2") (pinfunction "P$2_AV2") (pintype "bidirectional"))
    )
    (net (code "107") (name "Net-(DECAK-P$2)") (class "Default")
      (node (ref "BX1") (pin "1") (pinfunction "1_1") (pintype "passive"))
      (node (ref "DEC") (pin "BA1") (pinfunction "P$2_BA1") (pintype "bidirectional"))
      (node (ref "ECS") (pin "BA1") (pinfunction "P$2_BA1") (pintype "bidirectional"))
      (node (ref "EDAC") (pin "BA1") (pinfunction "P$2_BA1") (pintype "bidirectional"))
    )
    (net (code "108") (name "Net-(DECAL-P$2)") (class "Default")
      (node (ref "BX2") (pin "1") (pinfunction "1_1") (pintype "passive"))
      (node (ref "DEC") (pin "BA2") (pinfunction "P$2_BA2") (pintype "bidirectional"))
      (node (ref "ECS") (pin "BA2") (pinfunction "P$2_BA2") (pintype "bidirectional"))
      (node (ref "EDAC") (pin "BA2") (pinfunction "P$2_BA2") (pintype "bidirectional"))
    )
    (net (code "109") (name "Net-(DECAM-P$2)") (class "Default")
      (node (ref "BX1") (pin "3") (pinfunction "3_3") (pintype "passive"))
      (node (ref "DEC") (pin "BB1") (pinfunction "P$2_BB1") (pintype "bidirectional"))
      (node (ref "ECS") (pin "BB1") (pinfunction "P$2_BB1") (pintype "bidirectional"))
      (node (ref "EDAC") (pin "BB1") (pinfunction "P$2_BB1") (pintype "bidirectional"))
    )
    (net (code "110") (name "Net-(DECAN-P$2)") (class "Default")
      (node (ref "BX2") (pin "3") (pinfunction "3_3") (pintype "passive"))
      (node (ref "DEC") (pin "BB2") (pinfunction "P$2_BB2") (pintype "bidirectional"))
      (node (ref "ECS") (pin "BB2") (pinfunction "P$2_BB2") (pintype "bidirectional"))
      (node (ref "EDAC") (pin "BB2") (pinfunction "P$2_BB2") (pintype "bidirectional"))
    )
    (net (code "111") (name "Net-(DECAO-P$2)") (class "Default")
      (node (ref "BX1") (pin "5") (pinfunction "5_5") (pintype "passive"))
      (node (ref "DEC") (pin "BC1") (pinfunction "P$2_BC1") (pintype "bidirectional"))
      (node (ref "ECS") (pin "BC1") (pinfunction "P$2_BC1") (pintype "bidirectional"))
      (node (ref "EDAC") (pin "BC1") (pinfunction "P$2_BC1") (pintype "bidirectional"))
    )
    (net (code "112") (name "Net-(DECAP-P$2)") (class "Default")
      (node (ref "BX2") (pin "5") (pinfunction "5_5") (pintype "passive"))
      (node (ref "DEC") (pin "BC2") (pinfunction "P$2_BC2") (pintype "bidirectional"))
      (node (ref "ECS") (pin "BC2") (pinfunction "P$2_BC2") (pintype "bidirectional"))
      (node (ref "EDAC") (pin "BC2") (pinfunction "P$2_BC2") (pintype "bidirectional"))
    )
    (net (code "113") (name "Net-(DECAQ-P$2)") (class "Default")
      (node (ref "BX1") (pin "7") (pinfunction "7_7") (pintype "passive"))
      (node (ref "DEC") (pin "BD1") (pinfunction "P$2_BD1") (pintype "bidirectional"))
      (node (ref "ECS") (pin "BD1") (pinfunction "P$2_BD1") (pintype "bidirectional"))
      (node (ref "EDAC") (pin "BD1") (pinfunction "P$2_BD1") (pintype "bidirectional"))
    )
    (net (code "114") (name "Net-(DECAR-P$2)") (class "Default")
      (node (ref "BX2") (pin "7") (pinfunction "7_7") (pintype "passive"))
      (node (ref "DEC") (pin "BD2") (pinfunction "P$2_BD2") (pintype "bidirectional"))
      (node (ref "ECS") (pin "BD2") (pinfunction "P$2_BD2") (pintype "bidirectional"))
      (node (ref "EDAC") (pin "BD2") (pinfunction "P$2_BD2") (pintype "bidirectional"))
    )
    (net (code "115") (name "Net-(DECAS-P$2)") (class "Default")
      (node (ref "BX1") (pin "9") (pinfunction "9_9") (pintype "passive"))
      (node (ref "DEC") (pin "BE1") (pinfunction "P$2_BE1") (pintype "bidirectional"))
      (node (ref "ECS") (pin "BE1") (pinfunction "P$2_BE1") (pintype "bidirectional"))
      (node (ref "EDAC") (pin "BE1") (pinfunction "P$2_BE1") (pintype "bidirectional"))
    )
    (net (code "116") (name "Net-(DECAT-P$2)") (class "Default")
      (node (ref "BX2") (pin "9") (pinfunction "9_9") (pintype "passive"))
      (node (ref "DEC") (pin "BE2") (pinfunction "P$2_BE2") (pintype "bidirectional"))
      (node (ref "ECS") (pin "BE2") (pinfunction "P$2_BE2") (pintype "bidirectional"))
      (node (ref "EDAC") (pin "BE2") (pinfunction "P$2_BE2") (pintype "bidirectional"))
    )
    (net (code "117") (name "Net-(DECAU-P$2)") (class "Default")
      (node (ref "BX1") (pin "11") (pinfunction "11_11") (pintype "passive"))
      (node (ref "DEC") (pin "BF1") (pinfunction "P$2_BF1") (pintype "bidirectional"))
      (node (ref "ECS") (pin "BF1") (pinfunction "P$2_BF1") (pintype "bidirectional"))
      (node (ref "EDAC") (pin "BF1") (pinfunction "P$2_BF1") (pintype "bidirectional"))
    )
    (net (code "118") (name "Net-(DECAV-P$2)") (class "Default")
      (node (ref "BX2") (pin "11") (pinfunction "11_11") (pintype "passive"))
      (node (ref "DEC") (pin "BF2") (pinfunction "P$2_BF2") (pintype "bidirectional"))
      (node (ref "ECS") (pin "BF2") (pinfunction "P$2_BF2") (pintype "bidirectional"))
      (node (ref "EDAC") (pin "BF2") (pinfunction "P$2_BF2") (pintype "bidirectional"))
    )
    (net (code "119") (name "Net-(DECAW-P$2)") (class "Default")
      (node (ref "BX1") (pin "13") (pinfunction "13_13") (pintype "passive"))
      (node (ref "DEC") (pin "BH1") (pinfunction "P$2_BH1") (pintype "bidirectional"))
      (node (ref "ECS") (pin "BH1") (pinfunction "P$2_BH1") (pintype "bidirectional"))
      (node (ref "EDAC") (pin "BH1") (pinfunction "P$2_BH1") (pintype "bidirectional"))
    )
    (net (code "120") (name "Net-(DECAX-P$2)") (class "Default")
      (node (ref "BX2") (pin "13") (pinfunction "13_13") (pintype "passive"))
      (node (ref "DEC") (pin "BH2") (pinfunction "P$2_BH2") (pintype "bidirectional"))
      (node (ref "ECS") (pin "BH2") (pinfunction "P$2_BH2") (pintype "bidirectional"))
      (node (ref "EDAC") (pin "BH2") (pinfunction "P$2_BH2") (pintype "bidirectional"))
    )
    (net (code "121") (name "Net-(DECAY-P$2)") (class "Default")
      (node (ref "BX1") (pin "15") (pinfunction "15_15") (pintype "passive"))
      (node (ref "DEC") (pin "BJ1") (pinfunction "P$2_BJ1") (pintype "bidirectional"))
      (node (ref "ECS") (pin "BJ1") (pinfunction "P$2_BJ1") (pintype "bidirectional"))
      (node (ref "EDAC") (pin "BJ1") (pinfunction "P$2_BJ1") (pintype "bidirectional"))
    )
    (net (code "122") (name "Net-(DECAZ-P$2)") (class "Default")
      (node (ref "BX2") (pin "15") (pinfunction "15_15") (pintype "passive"))
      (node (ref "DEC") (pin "BJ2") (pinfunction "P$2_BJ2") (pintype "bidirectional"))
      (node (ref "ECS") (pin "BJ2") (pinfunction "P$2_BJ2") (pintype "bidirectional"))
      (node (ref "EDAC") (pin "BJ2") (pinfunction "P$2_BJ2") (pintype "bidirectional"))
    )
    (net (code "123") (name "Net-(DECB-P$2)") (class "Default")
      (node (ref "AX2") (pin "1") (pinfunction "1_1") (pintype "passive"))
      (node (ref "DEC") (pin "AA2") (pinfunction "P$2_AA2") (pintype "bidirectional"))
      (node (ref "ECS") (pin "AA2") (pinfunction "P$2_AA2") (pintype "bidirectional"))
      (node (ref "EDAC") (pin "AA2") (pinfunction "P$2_AA2") (pintype "bidirectional"))
    )
    (net (code "124") (name "Net-(DECBA-P$2)") (class "Default")
      (node (ref "BX1") (pin "17") (pinfunction "17_17") (pintype "passive"))
      (node (ref "DEC") (pin "BK1") (pinfunction "P$2_BK1") (pintype "bidirectional"))
      (node (ref "ECS") (pin "BK1") (pinfunction "P$2_BK1") (pintype "bidirectional"))
      (node (ref "EDAC") (pin "BK1") (pinfunction "P$2_BK1") (pintype "bidirectional"))
    )
    (net (code "125") (name "Net-(DECBB-P$2)") (class "Default")
      (node (ref "BX2") (pin "17") (pinfunction "17_17") (pintype "passive"))
      (node (ref "DEC") (pin "BK2") (pinfunction "P$2_BK2") (pintype "bidirectional"))
      (node (ref "ECS") (pin "BK2") (pinfunction "P$2_BK2") (pintype "bidirectional"))
      (node (ref "EDAC") (pin "BK2") (pinfunction "P$2_BK2") (pintype "bidirectional"))
    )
    (net (code "126") (name "Net-(DECBC-P$2)") (class "Default")
      (node (ref "BX1") (pin "19") (pinfunction "19_19") (pintype "passive"))
      (node (ref "DEC") (pin "BL1") (pinfunction "P$2_BL1") (pintype "bidirectional"))
      (node (ref "ECS") (pin "BL1") (pinfunction "P$2_BL1") (pintype "bidirectional"))
      (node (ref "EDAC") (pin "BL1") (pinfunction "P$2_BL1") (pintype "bidirectional"))
    )
    (net (code "127") (name "Net-(DECBD-P$2)") (class "Default")
      (node (ref "BX2") (pin "19") (pinfunction "19_19") (pintype "passive"))
      (node (ref "DEC") (pin "BL2") (pinfunction "P$2_BL2") (pintype "bidirectional"))
      (node (ref "ECS") (pin "BL2") (pinfunction "P$2_BL2") (pintype "bidirectional"))
      (node (ref "EDAC") (pin "BL2") (pinfunction "P$2_BL2") (pintype "bidirectional"))
    )
    (net (code "128") (name "Net-(DECBE-P$2)") (class "Default")
      (node (ref "BX1") (pin "21") (pinfunction "21_21") (pintype "passive"))
      (node (ref "DEC") (pin "BM1") (pinfunction "P$2_BM1") (pintype "bidirectional"))
      (node (ref "ECS") (pin "BM1") (pinfunction "P$2_BM1") (pintype "bidirectional"))
      (node (ref "EDAC") (pin "BM1") (pinfunction "P$2_BM1") (pintype "bidirectional"))
    )
    (net (code "129") (name "Net-(DECBF-P$2)") (class "Default")
      (node (ref "BX2") (pin "21") (pinfunction "21_21") (pintype "passive"))
      (node (ref "DEC") (pin "BM2") (pinfunction "P$2_BM2") (pintype "bidirectional"))
      (node (ref "ECS") (pin "BM2") (pinfunction "P$2_BM2") (pintype "bidirectional"))
      (node (ref "EDAC") (pin "BM2") (pinfunction "P$2_BM2") (pintype "bidirectional"))
    )
    (net (code "130") (name "Net-(DECBG-P$2)") (class "Default")
      (node (ref "BX1") (pin "23") (pinfunction "23_23") (pintype "passive"))
      (node (ref "DEC") (pin "BN1") (pinfunction "P$2_BN1") (pintype "bidirectional"))
      (node (ref "ECS") (pin "BN1") (pinfunction "P$2_BN1") (pintype "bidirectional"))
      (node (ref "EDAC") (pin "BN1") (pinfunction "P$2_BN1") (pintype "bidirectional"))
    )
    (net (code "131") (name "Net-(DECBH-P$2)") (class "Default")
      (node (ref "BX2") (pin "23") (pinfunction "23_23") (pintype "passive"))
      (node (ref "DEC") (pin "BN2") (pinfunction "P$2_BN2") (pintype "bidirectional"))
      (node (ref "ECS") (pin "BN2") (pinfunction "P$2_BN2") (pintype "bidirectional"))
      (node (ref "EDAC") (pin "BN2") (pinfunction "P$2_BN2") (pintype "bidirectional"))
    )
    (net (code "132") (name "Net-(DECBI-P$2)") (class "Default")
      (node (ref "BX1") (pin "25") (pinfunction "25_25") (pintype "passive"))
      (node (ref "DEC") (pin "BP1") (pinfunction "P$2_BP1") (pintype "bidirectional"))
      (node (ref "ECS") (pin "BP1") (pinfunction "P$2_BP1") (pintype "bidirectional"))
      (node (ref "EDAC") (pin "BP1") (pinfunction "P$2_BP1") (pintype "bidirectional"))
    )
    (net (code "133") (name "Net-(DECBJ-P$2)") (class "Default")
      (node (ref "BX2") (pin "25") (pinfunction "25_25") (pintype "passive"))
      (node (ref "DEC") (pin "BP2") (pinfunction "P$2_BP2") (pintype "bidirectional"))
      (node (ref "ECS") (pin "BP2") (pinfunction "P$2_BP2") (pintype "bidirectional"))
      (node (ref "EDAC") (pin "BP2") (pinfunction "P$2_BP2") (pintype "bidirectional"))
    )
    (net (code "134") (name "Net-(DECBK-P$2)") (class "Default")
      (node (ref "BX1") (pin "27") (pinfunction "27_27") (pintype "passive"))
      (node (ref "DEC") (pin "BR1") (pinfunction "P$2_BR1") (pintype "bidirectional"))
      (node (ref "ECS") (pin "BR1") (pinfunction "P$2_BR1") (pintype "bidirectional"))
      (node (ref "EDAC") (pin "BR1") (pinfunction "P$2_BR1") (pintype "bidirectional"))
    )
    (net (code "135") (name "Net-(DECBL-P$2)") (class "Default")
      (node (ref "BX2") (pin "27") (pinfunction "27_27") (pintype "passive"))
      (node (ref "DEC") (pin "BR2") (pinfunction "P$2_BR2") (pintype "bidirectional"))
      (node (ref "ECS") (pin "BR2") (pinfunction "P$2_BR2") (pintype "bidirectional"))
      (node (ref "EDAC") (pin "BR2") (pinfunction "P$2_BR2") (pintype "bidirectional"))
    )
    (net (code "136") (name "Net-(DECBM-P$2)") (class "Default")
      (node (ref "BX1") (pin "29") (pinfunction "29_29") (pintype "passive"))
      (node (ref "DEC") (pin "BS1") (pinfunction "P$2_BS1") (pintype "bidirectional"))
      (node (ref "ECS") (pin "BS1") (pinfunction "P$2_BS1") (pintype "bidirectional"))
      (node (ref "EDAC") (pin "BS1") (pinfunction "P$2_BS1") (pintype "bidirectional"))
    )
    (net (code "137") (name "Net-(DECBN-P$2)") (class "Default")
      (node (ref "BX2") (pin "29") (pinfunction "29_29") (pintype "passive"))
      (node (ref "DEC") (pin "BS2") (pinfunction "P$2_BS2") (pintype "bidirectional"))
      (node (ref "ECS") (pin "BS2") (pinfunction "P$2_BS2") (pintype "bidirectional"))
      (node (ref "EDAC") (pin "BS2") (pinfunction "P$2_BS2") (pintype "bidirectional"))
    )
    (net (code "138") (name "Net-(DECBO-P$2)") (class "Default")
      (node (ref "BX1") (pin "31") (pinfunction "31_31") (pintype "passive"))
      (node (ref "DEC") (pin "BT1") (pinfunction "P$2_BT1") (pintype "bidirectional"))
      (node (ref "ECS") (pin "BT1") (pinfunction "P$2_BT1") (pintype "bidirectional"))
      (node (ref "EDAC") (pin "BT1") (pinfunction "P$2_BT1") (pintype "bidirectional"))
    )
    (net (code "139") (name "Net-(DECBP-P$2)") (class "Default")
      (node (ref "BX2") (pin "31") (pinfunction "31_31") (pintype "passive"))
      (node (ref "DEC") (pin "BT2") (pinfunction "P$2_BT2") (pintype "bidirectional"))
      (node (ref "ECS") (pin "BT2") (pinfunction "P$2_BT2") (pintype "bidirectional"))
      (node (ref "EDAC") (pin "BT2") (pinfunction "P$2_BT2") (pintype "bidirectional"))
    )
    (net (code "140") (name "Net-(DECBQ-P$2)") (class "Default")
      (node (ref "BX1") (pin "33") (pinfunction "33_33") (pintype "passive"))
      (node (ref "DEC") (pin "BU1") (pinfunction "P$2_BU1") (pintype "bidirectional"))
      (node (ref "ECS") (pin "BU1") (pinfunction "P$2_BU1") (pintype "bidirectional"))
      (node (ref "EDAC") (pin "BU1") (pinfunction "P$2_BU1") (pintype "bidirectional"))
    )
    (net (code "141") (name "Net-(DECBR-P$2)") (class "Default")
      (node (ref "BX2") (pin "33") (pinfunction "33_33") (pintype "passive"))
      (node (ref "DEC") (pin "BU2") (pinfunction "P$2_BU2") (pintype "bidirectional"))
      (node (ref "ECS") (pin "BU2") (pinfunction "P$2_BU2") (pintype "bidirectional"))
      (node (ref "EDAC") (pin "BU2") (pinfunction "P$2_BU2") (pintype "bidirectional"))
    )
    (net (code "142") (name "Net-(DECBS-P$2)") (class "Default")
      (node (ref "BX1") (pin "35") (pinfunction "35_35") (pintype "passive"))
      (node (ref "DEC") (pin "BV1") (pinfunction "P$2_BV1") (pintype "bidirectional"))
      (node (ref "ECS") (pin "BV1") (pinfunction "P$2_BV1") (pintype "bidirectional"))
      (node (ref "EDAC") (pin "BV1") (pinfunction "P$2_BV1") (pintype "bidirectional"))
    )
    (net (code "143") (name "Net-(DECBT-P$2)") (class "Default")
      (node (ref "BX2") (pin "35") (pinfunction "35_35") (pintype "passive"))
      (node (ref "DEC") (pin "BV2") (pinfunction "P$2_BV2") (pintype "bidirectional"))
      (node (ref "ECS") (pin "BV2") (pinfunction "P$2_BV2") (pintype "bidirectional"))
      (node (ref "EDAC") (pin "BV2") (pinfunction "P$2_BV2") (pintype "bidirectional"))
    )
    (net (code "144") (name "Net-(DECC-P$2)") (class "Default")
      (node (ref "AX1") (pin "3") (pinfunction "3_3") (pintype "passive"))
      (node (ref "DEC") (pin "AB1") (pinfunction "P$2_AB1") (pintype "bidirectional"))
      (node (ref "ECS") (pin "AB1") (pinfunction "P$2_AB1") (pintype "bidirectional"))
      (node (ref "EDAC") (pin "AB1") (pinfunction "P$2_AB1") (pintype "bidirectional"))
    )
    (net (code "145") (name "Net-(DECD-P$2)") (class "Default")
      (node (ref "AX2") (pin "3") (pinfunction "3_3") (pintype "passive"))
      (node (ref "DEC") (pin "AB2") (pinfunction "P$2_AB2") (pintype "bidirectional"))
      (node (ref "ECS") (pin "AB2") (pinfunction "P$2_AB2") (pintype "bidirectional"))
      (node (ref "EDAC") (pin "AB2") (pinfunction "P$2_AB2") (pintype "bidirectional"))
    )
    (net (code "146") (name "Net-(DECE-P$2)") (class "Default")
      (node (ref "AX1") (pin "5") (pinfunction "5_5") (pintype "passive"))
      (node (ref "DEC") (pin "AC1") (pinfunction "P$2_AC1") (pintype "bidirectional"))
      (node (ref "ECS") (pin "AC1") (pinfunction "P$2_AC1") (pintype "bidirectional"))
      (node (ref "EDAC") (pin "AC1") (pinfunction "P$2_AC1") (pintype "bidirectional"))
    )
    (net (code "147") (name "Net-(DECF-P$2)") (class "Default")
      (node (ref "AX2") (pin "5") (pinfunction "5_5") (pintype "passive"))
      (node (ref "DEC") (pin "AC2") (pinfunction "P$2_AC2") (pintype "bidirectional"))
      (node (ref "ECS") (pin "AC2") (pinfunction "P$2_AC2") (pintype "bidirectional"))
      (node (ref "EDAC") (pin "AC2") (pinfunction "P$2_AC2") (pintype "bidirectional"))
    )
    (net (code "148") (name "Net-(DECG-P$2)") (class "Default")
      (node (ref "AX1") (pin "7") (pinfunction "7_7") (pintype "passive"))
      (node (ref "DEC") (pin "AD1") (pinfunction "P$2_AD1") (pintype "bidirectional"))
      (node (ref "ECS") (pin "AD1") (pinfunction "P$2_AD1") (pintype "bidirectional"))
      (node (ref "EDAC") (pin "AD1") (pinfunction "P$2_AD1") (pintype "bidirectional"))
    )
    (net (code "149") (name "Net-(DECH-P$2)") (class "Default")
      (node (ref "AX2") (pin "7") (pinfunction "7_7") (pintype "passive"))
      (node (ref "DEC") (pin "AD2") (pinfunction "P$2_AD2") (pintype "bidirectional"))
      (node (ref "ECS") (pin "AD2") (pinfunction "P$2_AD2") (pintype "bidirectional"))
      (node (ref "EDAC") (pin "AD2") (pinfunction "P$2_AD2") (pintype "bidirectional"))
    )
    (net (code "150") (name "Net-(DECI-P$2)") (class "Default")
      (node (ref "AX1") (pin "9") (pinfunction "9_9") (pintype "passive"))
      (node (ref "DEC") (pin "AE1") (pinfunction "P$2_AE1") (pintype "bidirectional"))
      (node (ref "ECS") (pin "AE1") (pinfunction "P$2_AE1") (pintype "bidirectional"))
      (node (ref "EDAC") (pin "AE1") (pinfunction "P$2_AE1") (pintype "bidirectional"))
    )
    (net (code "151") (name "Net-(DECJ-P$2)") (class "Default")
      (node (ref "AX2") (pin "9") (pinfunction "9_9") (pintype "passive"))
      (node (ref "DEC") (pin "AE2") (pinfunction "P$2_AE2") (pintype "bidirectional"))
      (node (ref "ECS") (pin "AE2") (pinfunction "P$2_AE2") (pintype "bidirectional"))
      (node (ref "EDAC") (pin "AE2") (pinfunction "P$2_AE2") (pintype "bidirectional"))
    )
    (net (code "152") (name "Net-(DECK-P$2)") (class "Default")
      (node (ref "AX1") (pin "11") (pinfunction "11_11") (pintype "passive"))
      (node (ref "DEC") (pin "AF1") (pinfunction "P$2_AF1") (pintype "bidirectional"))
      (node (ref "ECS") (pin "AF1") (pinfunction "P$2_AF1") (pintype "bidirectional"))
      (node (ref "EDAC") (pin "AF1") (pinfunction "P$2_AF1") (pintype "bidirectional"))
    )
    (net (code "153") (name "Net-(DECL-P$2)") (class "Default")
      (node (ref "AX2") (pin "11") (pinfunction "11_11") (pintype "passive"))
      (node (ref "DEC") (pin "AF2") (pinfunction "P$2_AF2") (pintype "bidirectional"))
      (node (ref "ECS") (pin "AF2") (pinfunction "P$2_AF2") (pintype "bidirectional"))
      (node (ref "EDAC") (pin "AF2") (pinfunction "P$2_AF2") (pintype "bidirectional"))
    )
    (net (code "154") (name "Net-(DECM-P$2)") (class "Default")
      (node (ref "AX1") (pin "13") (pinfunction "13_13") (pintype "passive"))
      (node (ref "DEC") (pin "AH1") (pinfunction "P$2_AH1") (pintype "bidirectional"))
      (node (ref "ECS") (pin "AH1") (pinfunction "P$2_AH1") (pintype "bidirectional"))
      (node (ref "EDAC") (pin "AH1") (pinfunction "P$2_AH1") (pintype "bidirectional"))
    )
    (net (code "155") (name "Net-(DECN-P$2)") (class "Default")
      (node (ref "AX2") (pin "13") (pinfunction "13_13") (pintype "passive"))
      (node (ref "DEC") (pin "AH2") (pinfunction "P$2_AH2") (pintype "bidirectional"))
      (node (ref "ECS") (pin "AH2") (pinfunction "P$2_AH2") (pintype "bidirectional"))
      (node (ref "EDAC") (pin "AH2") (pinfunction "P$2_AH2") (pintype "bidirectional"))
    )
    (net (code "156") (name "Net-(DECO-P$2)") (class "Default")
      (node (ref "AX1") (pin "15") (pinfunction "15_15") (pintype "passive"))
      (node (ref "DEC") (pin "AJ1") (pinfunction "P$2_AJ1") (pintype "bidirectional"))
      (node (ref "ECS") (pin "AJ1") (pinfunction "P$2_AJ1") (pintype "bidirectional"))
      (node (ref "EDAC") (pin "AJ1") (pinfunction "P$2_AJ1") (pintype "bidirectional"))
    )
    (net (code "157") (name "Net-(DECP-P$2)") (class "Default")
      (node (ref "AX2") (pin "15") (pinfunction "15_15") (pintype "passive"))
      (node (ref "DEC") (pin "AJ2") (pinfunction "P$2_AJ2") (pintype "bidirectional"))
      (node (ref "ECS") (pin "AJ2") (pinfunction "P$2_AJ2") (pintype "bidirectional"))
      (node (ref "EDAC") (pin "AJ2") (pinfunction "P$2_AJ2") (pintype "bidirectional"))
    )
    (net (code "158") (name "Net-(DECQ-P$2)") (class "Default")
      (node (ref "AX1") (pin "17") (pinfunction "17_17") (pintype "passive"))
      (node (ref "DEC") (pin "AK1") (pinfunction "P$2_AK1") (pintype "bidirectional"))
      (node (ref "ECS") (pin "AK1") (pinfunction "P$2_AK1") (pintype "bidirectional"))
      (node (ref "EDAC") (pin "AK1") (pinfunction "P$2_AK1") (pintype "bidirectional"))
    )
    (net (code "159") (name "Net-(DECR-P$2)") (class "Default")
      (node (ref "AX2") (pin "17") (pinfunction "17_17") (pintype "passive"))
      (node (ref "DEC") (pin "AK2") (pinfunction "P$2_AK2") (pintype "bidirectional"))
      (node (ref "ECS") (pin "AK2") (pinfunction "P$2_AK2") (pintype "bidirectional"))
      (node (ref "EDAC") (pin "AK2") (pinfunction "P$2_AK2") (pintype "bidirectional"))
    )
    (net (code "160") (name "Net-(DECS-P$2)") (class "Default")
      (node (ref "AX1") (pin "19") (pinfunction "19_19") (pintype "passive"))
      (node (ref "DEC") (pin "AL1") (pinfunction "P$2_AL1") (pintype "bidirectional"))
      (node (ref "ECS") (pin "AL1") (pinfunction "P$2_AL1") (pintype "bidirectional"))
      (node (ref "EDAC") (pin "AL1") (pinfunction "P$2_AL1") (pintype "bidirectional"))
    )
    (net (code "161") (name "Net-(DECT-P$2)") (class "Default")
      (node (ref "AX2") (pin "19") (pinfunction "19_19") (pintype "passive"))
      (node (ref "DEC") (pin "AL2") (pinfunction "P$2_AL2") (pintype "bidirectional"))
      (node (ref "ECS") (pin "AL2") (pinfunction "P$2_AL2") (pintype "bidirectional"))
      (node (ref "EDAC") (pin "AL2") (pinfunction "P$2_AL2") (pintype "bidirectional"))
    )
    (net (code "162") (name "Net-(DECU-P$2)") (class "Default")
      (node (ref "AX1") (pin "21") (pinfunction "21_21") (pintype "passive"))
      (node (ref "DEC") (pin "AM1") (pinfunction "P$2_AM1") (pintype "bidirectional"))
      (node (ref "ECS") (pin "AM1") (pinfunction "P$2_AM1") (pintype "bidirectional"))
      (node (ref "EDAC") (pin "AM1") (pinfunction "P$2_AM1") (pintype "bidirectional"))
    )
    (net (code "163") (name "Net-(DECV-P$2)") (class "Default")
      (node (ref "AX2") (pin "21") (pinfunction "21_21") (pintype "passive"))
      (node (ref "DEC") (pin "AM2") (pinfunction "P$2_AM2") (pintype "bidirectional"))
      (node (ref "ECS") (pin "AM2") (pinfunction "P$2_AM2") (pintype "bidirectional"))
      (node (ref "EDAC") (pin "AM2") (pinfunction "P$2_AM2") (pintype "bidirectional"))
    )
    (net (code "164") (name "Net-(DECW-P$2)") (class "Default")
      (node (ref "AX1") (pin "23") (pinfunction "23_23") (pintype "passive"))
      (node (ref "DEC") (pin "AN1") (pinfunction "P$2_AN1") (pintype "bidirectional"))
      (node (ref "ECS") (pin "AN1") (pinfunction "P$2_AN1") (pintype "bidirectional"))
      (node (ref "EDAC") (pin "AN1") (pinfunction "P$2_AN1") (pintype "bidirectional"))
    )
    (net (code "165") (name "Net-(DECX-P$2)") (class "Default")
      (node (ref "AX2") (pin "23") (pinfunction "23_23") (pintype "passive"))
      (node (ref "DEC") (pin "AN2") (pinfunction "P$2_AN2") (pintype "bidirectional"))
      (node (ref "ECS") (pin "AN2") (pinfunction "P$2_AN2") (pintype "bidirectional"))
      (node (ref "EDAC") (pin "AN2") (pinfunction "P$2_AN2") (pintype "bidirectional"))
    )
    (net (code "166") (name "Net-(DECY-P$2)") (class "Default")
      (node (ref "AX1") (pin "25") (pinfunction "25_25") (pintype "passive"))
      (node (ref "DEC") (pin "AP1") (pinfunction "P$2_AP1") (pintype "bidirectional"))
      (node (ref "ECS") (pin "AP1") (pinfunction "P$2_AP1") (pintype "bidirectional"))
      (node (ref "EDAC") (pin "AP1") (pinfunction "P$2_AP1") (pintype "bidirectional"))
    )
    (net (code "167") (name "Net-(DECZ-P$2)") (class "Default")
      (node (ref "AX2") (pin "25") (pinfunction "25_25") (pintype "passive"))
      (node (ref "DEC") (pin "AP2") (pinfunction "P$2_AP2") (pintype "bidirectional"))
      (node (ref "ECS") (pin "AP2") (pinfunction "P$2_AP2") (pintype "bidirectional"))
      (node (ref "EDAC") (pin "AP2") (pinfunction "P$2_AP2") (pintype "bidirectional"))
    )
    (net (code "168") (name "Net-(GREEN-C)") (class "Default")
      (node (ref "GREEN") (pin "K") (pinfunction "C_K") (pintype "passive"))
      (node (ref "R2") (pin "2") (pinfunction "2_2") (pintype "passive"))
    )
    (net (code "169") (name "Net-(LOADHI1-Pad1)") (class "Default")
      (node (ref "LOADHI1") (pin "1") (pinfunction "1_1") (pintype "passive"))
      (node (ref "R11") (pin "2") (pinfunction "2_2") (pintype "passive"))
    )
    (net (code "170") (name "Net-(LOADHI3-Pad1)") (class "Default")
      (node (ref "LOADHI3") (pin "1") (pinfunction "1_1") (pintype "passive"))
      (node (ref "R10") (pin "2") (pinfunction "2_2") (pintype "passive"))
    )
    (net (code "171") (name "Net-(LOADL1-Pad1)") (class "Default")
      (node (ref "LOADL1") (pin "1") (pinfunction "1_1") (pintype "passive"))
      (node (ref "R8") (pin "1") (pinfunction "1_1") (pintype "passive"))
      (node (ref "R9") (pin "1") (pinfunction "1_1") (pintype "passive"))
    )
    (net (code "172") (name "Net-(LOADL3-Pad1)") (class "Default")
      (node (ref "LOADL3") (pin "1") (pinfunction "1_1") (pintype "passive"))
      (node (ref "R6") (pin "1") (pinfunction "1_1") (pintype "passive"))
      (node (ref "R7") (pin "1") (pinfunction "1_1") (pintype "passive"))
    )
    (net (code "173") (name "Net-(PWR-C)") (class "Default")
      (node (ref "PWR") (pin "K") (pinfunction "C_K") (pintype "passive"))
      (node (ref "R14") (pin "2") (pinfunction "2_2") (pintype "passive"))
    )
    (net (code "174") (name "Net-(RED1-C)") (class "Default")
      (node (ref "R3") (pin "2") (pinfunction "2_2") (pintype "passive"))
      (node (ref "RED1") (pin "K") (pinfunction "C_K") (pintype "passive"))
    )
    (net (code "175") (name "Net-(RED2-C)") (class "Default")
      (node (ref "R5") (pin "2") (pinfunction "2_2") (pintype "passive"))
      (node (ref "RED2") (pin "K") (pinfunction "C_K") (pintype "passive"))
    )
    (net (code "176") (name "Net-(UUT_PWR-C)") (class "Default")
      (node (ref "R12") (pin "2") (pinfunction "2_2") (pintype "passive"))
      (node (ref "R13") (pin "2") (pinfunction "2_2") (pintype "passive"))
      (node (ref "UUT_PWR") (pin "K") (pinfunction "C_K") (pintype "passive"))
    )
    (net (code "177") (name "Net-(YELLOW-C)") (class "Default")
      (node (ref "R4") (pin "2") (pinfunction "2_2") (pintype "passive"))
      (node (ref "YELLOW") (pin "K") (pinfunction "C_K") (pintype "passive"))
    )
    (net (code "178") (name "VCC") (class "Default")
      (node (ref "D1") (pin "A") (pinfunction "A_A") (pintype "passive"))
      (node (ref "POWER") (pin "3") (pinfunction "3_3") (pintype "passive"))
      (node (ref "R6") (pin "2") (pinfunction "2_2") (pintype "passive"))
      (node (ref "R7") (pin "2") (pinfunction "2_2") (pintype "passive"))
      (node (ref "R8") (pin "2") (pinfunction "2_2") (pintype "passive"))
      (node (ref "R9") (pin "2") (pinfunction "2_2") (pintype "passive"))
      (node (ref "UUT") (pin "2") (pinfunction "P_2") (pintype "passive"))
    )
    (net (code "179") (name "VDD") (class "Default")
      (node (ref "C2") (pin "1") (pinfunction "1_1") (pintype "passive"))
      (node (ref "C3") (pin "1") (pinfunction "1_1") (pintype "passive"))
      (node (ref "C4") (pin "1") (pinfunction "1_1") (pintype "passive"))
      (node (ref "C5") (pin "1") (pinfunction "1_1") (pintype "passive"))
      (node (ref "C6") (pin "1") (pinfunction "1_1") (pintype "passive"))
      (node (ref "C7") (pin "1") (pinfunction "1_1") (pintype "passive"))
      (node (ref "D2") (pin "C") (pinfunction "C_C") (pintype "passive"))
      (node (ref "IC1") (pin "9") (pinfunction "VDD_9") (pintype "power_in"))
      (node (ref "IC2") (pin "9") (pinfunction "VDD_9") (pintype "power_in"))
      (node (ref "IC3") (pin "9") (pinfunction "VDD_9") (pintype "power_in"))
      (node (ref "IC4") (pin "9") (pinfunction "VDD_9") (pintype "power_in"))
      (node (ref "IC5") (pin "9") (pinfunction "VDD_9") (pintype "power_in"))
      (node (ref "PWR") (pin "A") (pinfunction "A_A") (pintype "passive"))
    )
    (net (code "180") (name "VPP") (class "Default")
      (node (ref "AX2") (pin "2") (pinfunction "2_2") (pintype "passive"))
      (node (ref "BX2") (pin "2") (pinfunction "2_2") (pintype "passive"))
      (node (ref "C1") (pin "+") (pinfunction "+_+") (pintype "passive"))
      (node (ref "IC3") (pin "23") (pinfunction "GPA2_23") (pintype "bidirectional"))
      (node (ref "R1") (pin "2") (pinfunction "2_2") (pintype "passive"))
      (node (ref "UUT") (pin "3") (pinfunction "S_3") (pintype "passive"))
      (node (ref "UUT_PWR") (pin "A") (pinfunction "A_A") (pintype "passive"))
      (node (ref "VPP") (pin "1") (pinfunction "1_1") (pintype "passive"))
    )
    (net (code "181") (name "unconnected-(IC1-INTA-Pad20)") (class "Default")
      (node (ref "IC1") (pin "20") (pinfunction "INTA_20") (pintype "output"))
    )
    (net (code "182") (name "unconnected-(IC1-INTB-Pad19)") (class "Default")
      (node (ref "IC1") (pin "19") (pinfunction "INTB_19") (pintype "output"))
    )
    (net (code "183") (name "unconnected-(IC2-INTA-Pad20)") (class "Default")
      (node (ref "IC2") (pin "20") (pinfunction "INTA_20") (pintype "output"))
    )
    (net (code "184") (name "unconnected-(IC2-INTB-Pad19)") (class "Default")
      (node (ref "IC2") (pin "19") (pinfunction "INTB_19") (pintype "output"))
    )
    (net (code "185") (name "unconnected-(IC3-INTA-Pad20)") (class "Default")
      (node (ref "IC3") (pin "20") (pinfunction "INTA_20") (pintype "output"))
    )
    (net (code "186") (name "unconnected-(IC3-INTB-Pad19)") (class "Default")
      (node (ref "IC3") (pin "19") (pinfunction "INTB_19") (pintype "output"))
    )
    (net (code "187") (name "unconnected-(IC4-INTA-Pad20)") (class "Default")
      (node (ref "IC4") (pin "20") (pinfunction "INTA_20") (pintype "output"))
    )
    (net (code "188") (name "unconnected-(IC4-INTB-Pad19)") (class "Default")
      (node (ref "IC4") (pin "19") (pinfunction "INTB_19") (pintype "output"))
    )
    (net (code "189") (name "unconnected-(IC5-INTA-Pad20)") (class "Default")
      (node (ref "IC5") (pin "20") (pinfunction "INTA_20") (pintype "output"))
    )
    (net (code "190") (name "unconnected-(IC5-INTB-Pad19)") (class "Default")
      (node (ref "IC5") (pin "19") (pinfunction "INTB_19") (pintype "output"))
    )
    (net (code "191") (name "unconnected-(PC1-Pad1)") (class "Default")
      (node (ref "PC1") (pin "1") (pinfunction "1_1") (pintype "passive"))
    )
    (net (code "192") (name "unconnected-(PC1-Pad2)") (class "Default")
      (node (ref "PC1") (pin "2") (pinfunction "2_2") (pintype "passive"))
    )
    (net (code "193") (name "unconnected-(PC1-Pad5)") (class "Default")
      (node (ref "PC1") (pin "5") (pinfunction "5_5") (pintype "passive"))
    )
    (net (code "194") (name "unconnected-(PC1-Pad7)") (class "Default")
      (node (ref "PC1") (pin "7") (pinfunction "7_7") (pintype "passive"))
    )
    (net (code "195") (name "unconnected-(POWER-Pad4)") (class "Default")
      (node (ref "POWER") (pin "4") (pinfunction "4_4") (pintype "passive"))
    )
    (net (code "196") (name "unconnected-(POWER-Pad5)") (class "Default")
      (node (ref "POWER") (pin "5") (pinfunction "5_5") (pintype "passive"))
    )
    (net (code "197") (name "unconnected-(POWER-Pad6)") (class "Default")
      (node (ref "POWER") (pin "6") (pinfunction "6_6") (pintype "passive"))
    )
    (net (code "198") (name "unconnected-(UUTA-O-Pad1)") (class "Default")
      (node (ref "UUT") (pin "1") (pinfunction "O_1") (pintype "passive"))
    )
  )
)
